# Horloge_Display.net
KiCad netlist of a schematic drawn in Altium Designer
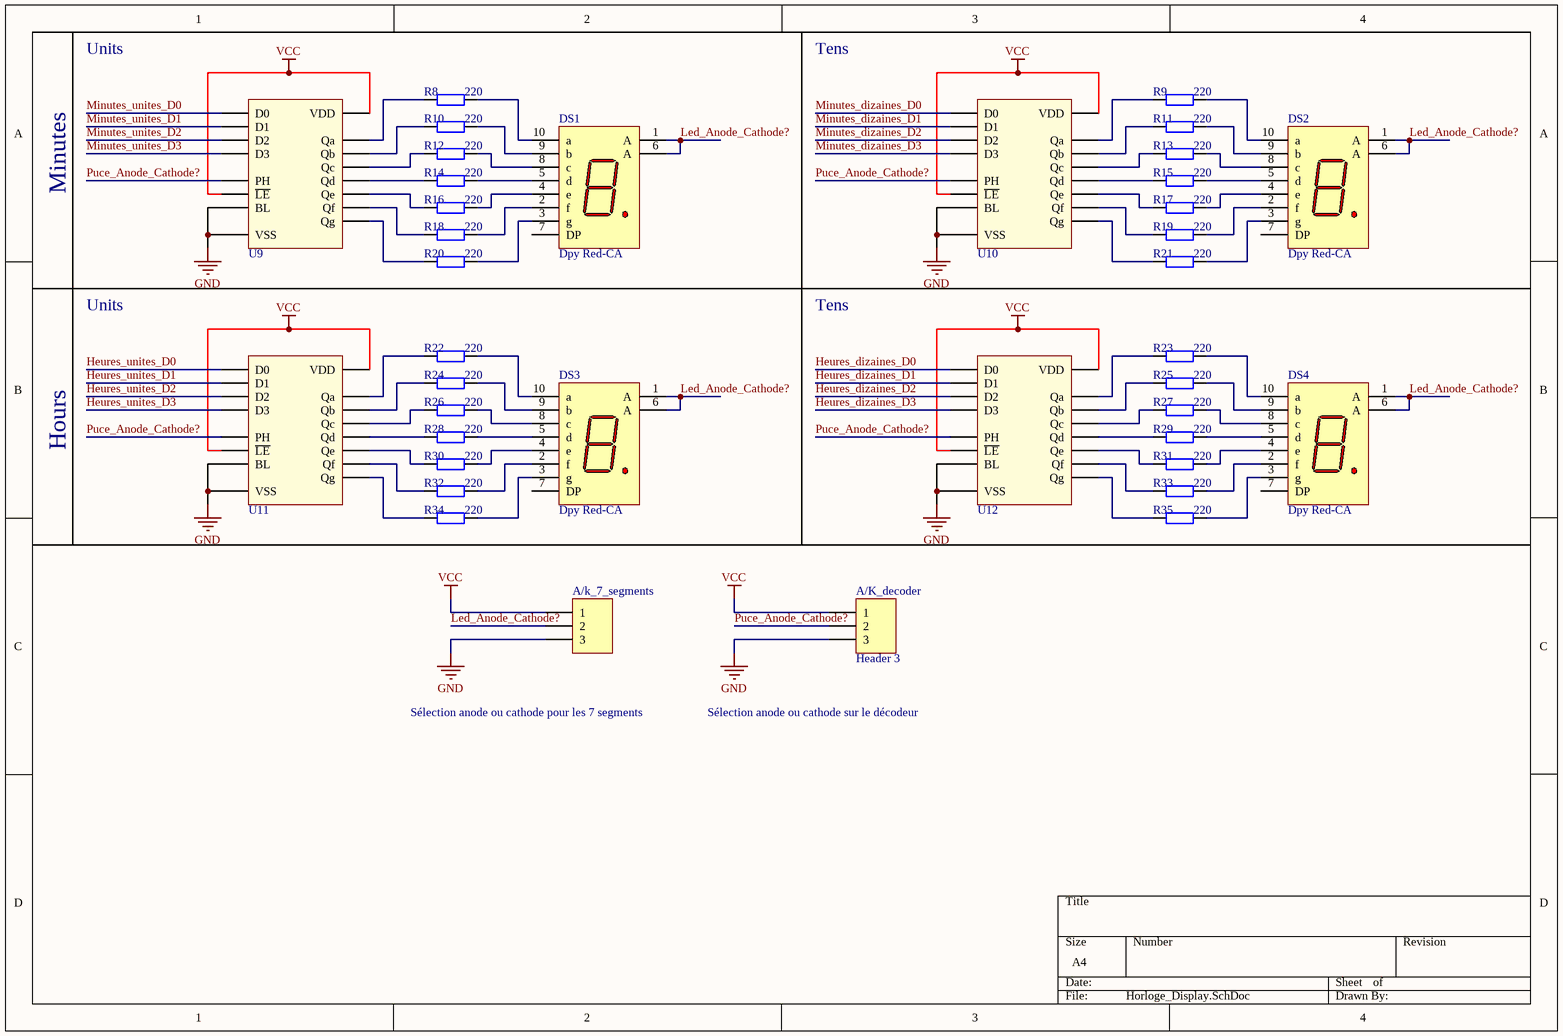
[diagram p0: Horloge_Display.SchDoc]

(export (version "E")
  (design (tool "Eeschema 10.0.6"))
  (components
    (comp (ref "A/k_7_segments")
      (value "Common_7-segments")
      (footprint "HDR1X3")
      (description "Header, 3-Pin")
      (fields (field (name "PUBLISHER") "Altium Limited"))
      (libsource (lib "Miscellaneous Connectors") (part "Header 3"))
    )
    (comp (ref "A/K_decoder")
      (value "Header 3")
      (footprint "HDR1X3")
      (description "Header, 3-Pin")
      (fields (field (name "PUBLISHER") "Altium Limited"))
      (libsource (lib "Miscellaneous Connectors") (part "Header 3"))
    )
    (comp (ref "DS1")
      (value "Dpy Red-CA")
      (footprint "7 segments 5082-7731")
      (description "7.62 mm Black Surface HER 7-Segment Display: CA, RH DP")
      (fields (field (name "PUBLISHER") "Altium Limited"))
      (libsource (lib "Miscellaneous Devices") (part "Dpy Red-CA"))
    )
    (comp (ref "DS2")
      (value "Dpy Red-CA")
      (footprint "7 segments 5082-7731")
      (description "7.62 mm Black Surface HER 7-Segment Display: CA, RH DP")
      (fields (field (name "PUBLISHER") "Altium Limited"))
      (libsource (lib "Miscellaneous Devices") (part "Dpy Red-CA"))
    )
    (comp (ref "DS3")
      (value "Dpy Red-CA")
      (footprint "7 segments 5082-7731")
      (description "7.62 mm Black Surface HER 7-Segment Display: CA, RH DP")
      (fields (field (name "PUBLISHER") "Altium Limited"))
      (libsource (lib "Miscellaneous Devices") (part "Dpy Red-CA"))
    )
    (comp (ref "DS4")
      (value "Dpy Red-CA")
      (footprint "7 segments 5082-7731")
      (description "7.62 mm Black Surface HER 7-Segment Display: CA, RH DP")
      (fields (field (name "PUBLISHER") "Altium Limited"))
      (libsource (lib "Miscellaneous Devices") (part "Dpy Red-CA"))
    )
    (comp (ref "R8")
      (value "220")
      (footprint "Resistor 1206")
      (description "Resistor")
      (fields (field (name "Comment") "Res2") (field (name "PUBLISHER") "Altium Limited"))
      (libsource (lib "Miscellaneous Devices") (part "Res2"))
    )
    (comp (ref "R9")
      (value "220")
      (footprint "Resistor 1206")
      (description "Resistor")
      (fields (field (name "Comment") "Res2") (field (name "PUBLISHER") "Altium Limited"))
      (libsource (lib "Miscellaneous Devices") (part "Res2"))
    )
    (comp (ref "R10")
      (value "220")
      (footprint "Resistor 1206")
      (description "Resistor")
      (fields (field (name "Comment") "Res2") (field (name "PUBLISHER") "Altium Limited"))
      (libsource (lib "Miscellaneous Devices") (part "Res2"))
    )
    (comp (ref "R11")
      (value "220")
      (footprint "Resistor 1206")
      (description "Resistor")
      (fields (field (name "Comment") "Res2") (field (name "PUBLISHER") "Altium Limited"))
      (libsource (lib "Miscellaneous Devices") (part "Res2"))
    )
    (comp (ref "R12")
      (value "220")
      (footprint "Resistor 1206")
      (description "Resistor")
      (fields (field (name "Comment") "Res2") (field (name "PUBLISHER") "Altium Limited"))
      (libsource (lib "Miscellaneous Devices") (part "Res2"))
    )
    (comp (ref "R13")
      (value "220")
      (footprint "Resistor 1206")
      (description "Resistor")
      (fields (field (name "Comment") "Res2") (field (name "PUBLISHER") "Altium Limited"))
      (libsource (lib "Miscellaneous Devices") (part "Res2"))
    )
    (comp (ref "R14")
      (value "220")
      (footprint "Resistor 1206")
      (description "Resistor")
      (fields (field (name "Comment") "Res2") (field (name "PUBLISHER") "Altium Limited"))
      (libsource (lib "Miscellaneous Devices") (part "Res2"))
    )
    (comp (ref "R15")
      (value "220")
      (footprint "Resistor 1206")
      (description "Resistor")
      (fields (field (name "Comment") "Res2") (field (name "PUBLISHER") "Altium Limited"))
      (libsource (lib "Miscellaneous Devices") (part "Res2"))
    )
    (comp (ref "R16")
      (value "220")
      (footprint "Resistor 1206")
      (description "Resistor")
      (fields (field (name "Comment") "Res2") (field (name "PUBLISHER") "Altium Limited"))
      (libsource (lib "Miscellaneous Devices") (part "Res2"))
    )
    (comp (ref "R17")
      (value "220")
      (footprint "Resistor 1206")
      (description "Resistor")
      (fields (field (name "Comment") "Res2") (field (name "PUBLISHER") "Altium Limited"))
      (libsource (lib "Miscellaneous Devices") (part "Res2"))
    )
    (comp (ref "R18")
      (value "220")
      (footprint "Resistor 1206")
      (description "Resistor")
      (fields (field (name "Comment") "Res2") (field (name "PUBLISHER") "Altium Limited"))
      (libsource (lib "Miscellaneous Devices") (part "Res2"))
    )
    (comp (ref "R19")
      (value "220")
      (footprint "Resistor 1206")
      (description "Resistor")
      (fields (field (name "Comment") "Res2") (field (name "PUBLISHER") "Altium Limited"))
      (libsource (lib "Miscellaneous Devices") (part "Res2"))
    )
    (comp (ref "R20")
      (value "220")
      (footprint "Resistor 1206")
      (description "Resistor")
      (fields (field (name "Comment") "Res2") (field (name "PUBLISHER") "Altium Limited"))
      (libsource (lib "Miscellaneous Devices") (part "Res2"))
    )
    (comp (ref "R21")
      (value "220")
      (footprint "Resistor 1206")
      (description "Resistor")
      (fields (field (name "Comment") "Res2") (field (name "PUBLISHER") "Altium Limited"))
      (libsource (lib "Miscellaneous Devices") (part "Res2"))
    )
    (comp (ref "R22")
      (value "220")
      (footprint "Resistor 1206")
      (description "Resistor")
      (fields (field (name "Comment") "Res2") (field (name "PUBLISHER") "Altium Limited"))
      (libsource (lib "Miscellaneous Devices") (part "Res2"))
    )
    (comp (ref "R23")
      (value "220")
      (footprint "Resistor 1206")
      (description "Resistor")
      (fields (field (name "Comment") "Res2") (field (name "PUBLISHER") "Altium Limited"))
      (libsource (lib "Miscellaneous Devices") (part "Res2"))
    )
    (comp (ref "R24")
      (value "220")
      (footprint "Resistor 1206")
      (description "Resistor")
      (fields (field (name "Comment") "Res2") (field (name "PUBLISHER") "Altium Limited"))
      (libsource (lib "Miscellaneous Devices") (part "Res2"))
    )
    (comp (ref "R25")
      (value "220")
      (footprint "Resistor 1206")
      (description "Resistor")
      (fields (field (name "Comment") "Res2") (field (name "PUBLISHER") "Altium Limited"))
      (libsource (lib "Miscellaneous Devices") (part "Res2"))
    )
    (comp (ref "R26")
      (value "220")
      (footprint "Resistor 1206")
      (description "Resistor")
      (fields (field (name "Comment") "Res2") (field (name "PUBLISHER") "Altium Limited"))
      (libsource (lib "Miscellaneous Devices") (part "Res2"))
    )
    (comp (ref "R27")
      (value "220")
      (footprint "Resistor 1206")
      (description "Resistor")
      (fields (field (name "Comment") "Res2") (field (name "PUBLISHER") "Altium Limited"))
      (libsource (lib "Miscellaneous Devices") (part "Res2"))
    )
    (comp (ref "R28")
      (value "220")
      (footprint "Resistor 1206")
      (description "Resistor")
      (fields (field (name "Comment") "Res2") (field (name "PUBLISHER") "Altium Limited"))
      (libsource (lib "Miscellaneous Devices") (part "Res2"))
    )
    (comp (ref "R29")
      (value "220")
      (footprint "Resistor 1206")
      (description "Resistor")
      (fields (field (name "Comment") "Res2") (field (name "PUBLISHER") "Altium Limited"))
      (libsource (lib "Miscellaneous Devices") (part "Res2"))
    )
    (comp (ref "R30")
      (value "220")
      (footprint "Resistor 1206")
      (description "Resistor")
      (fields (field (name "Comment") "Res2") (field (name "PUBLISHER") "Altium Limited"))
      (libsource (lib "Miscellaneous Devices") (part "Res2"))
    )
    (comp (ref "R31")
      (value "220")
      (footprint "Resistor 1206")
      (description "Resistor")
      (fields (field (name "Comment") "Res2") (field (name "PUBLISHER") "Altium Limited"))
      (libsource (lib "Miscellaneous Devices") (part "Res2"))
    )
    (comp (ref "R32")
      (value "220")
      (footprint "Resistor 1206")
      (description "Resistor")
      (fields (field (name "Comment") "Res2") (field (name "PUBLISHER") "Altium Limited"))
      (libsource (lib "Miscellaneous Devices") (part "Res2"))
    )
    (comp (ref "R33")
      (value "220")
      (footprint "Resistor 1206")
      (description "Resistor")
      (fields (field (name "Comment") "Res2") (field (name "PUBLISHER") "Altium Limited"))
      (libsource (lib "Miscellaneous Devices") (part "Res2"))
    )
    (comp (ref "R34")
      (value "220")
      (footprint "Resistor 1206")
      (description "Resistor")
      (fields (field (name "Comment") "Res2") (field (name "PUBLISHER") "Altium Limited"))
      (libsource (lib "Miscellaneous Devices") (part "Res2"))
    )
    (comp (ref "R35")
      (value "220")
      (footprint "Resistor 1206")
      (description "Resistor")
      (fields (field (name "Comment") "Res2") (field (name "PUBLISHER") "Altium Limited"))
      (libsource (lib "Miscellaneous Devices") (part "Res2"))
    )
    (comp (ref "U9")
      (value "7 segment driver")
      (footprint "HEF4543")
      (libsource (lib "Robot_2020") (part "HEF4543B"))
    )
    (comp (ref "U10")
      (value "7 segment driver")
      (footprint "HEF4543")
      (libsource (lib "Robot_2020") (part "HEF4543B"))
    )
    (comp (ref "U11")
      (value "7 segment driver")
      (footprint "HEF4543")
      (libsource (lib "Robot_2020") (part "HEF4543B"))
    )
    (comp (ref "U12")
      (value "7 segment driver")
      (footprint "HEF4543")
      (libsource (lib "Robot_2020") (part "HEF4543B"))
    )
  )
  (nets
    (net (code "1") (name "/Heures_dizaines_D0") (class "Default")
      (node (ref "U12") (pin "5") (pinfunction "D0_5") (pintype "passive"))
    )
    (net (code "2") (name "/Heures_dizaines_D1") (class "Default")
      (node (ref "U12") (pin "3") (pinfunction "D1_3") (pintype "passive"))
    )
    (net (code "3") (name "/Heures_dizaines_D2") (class "Default")
      (node (ref "U12") (pin "2") (pinfunction "D2_2") (pintype "passive"))
    )
    (net (code "4") (name "/Heures_dizaines_D3") (class "Default")
      (node (ref "U12") (pin "4") (pinfunction "D3_4") (pintype "passive"))
    )
    (net (code "5") (name "/Heures_unites_D0") (class "Default")
      (node (ref "U11") (pin "5") (pinfunction "D0_5") (pintype "passive"))
    )
    (net (code "6") (name "/Heures_unites_D1") (class "Default")
      (node (ref "U11") (pin "3") (pinfunction "D1_3") (pintype "passive"))
    )
    (net (code "7") (name "/Heures_unites_D2") (class "Default")
      (node (ref "U11") (pin "2") (pinfunction "D2_2") (pintype "passive"))
    )
    (net (code "8") (name "/Heures_unites_D3") (class "Default")
      (node (ref "U11") (pin "4") (pinfunction "D3_4") (pintype "passive"))
    )
    (net (code "9") (name "/Led_Anode_Cathode?") (class "Default")
      (node (ref "A/k_7_segments") (pin "2") (pinfunction "2_2") (pintype "passive"))
      (node (ref "DS1") (pin "1") (pinfunction "A_1") (pintype "passive"))
      (node (ref "DS1") (pin "6") (pinfunction "A_6") (pintype "passive"))
      (node (ref "DS2") (pin "1") (pinfunction "A_1") (pintype "passive"))
      (node (ref "DS2") (pin "6") (pinfunction "A_6") (pintype "passive"))
      (node (ref "DS3") (pin "1") (pinfunction "A_1") (pintype "passive"))
      (node (ref "DS3") (pin "6") (pinfunction "A_6") (pintype "passive"))
      (node (ref "DS4") (pin "1") (pinfunction "A_1") (pintype "passive"))
      (node (ref "DS4") (pin "6") (pinfunction "A_6") (pintype "passive"))
    )
    (net (code "10") (name "/Minutes_dizaines_D0") (class "Default")
      (node (ref "U10") (pin "5") (pinfunction "D0_5") (pintype "passive"))
    )
    (net (code "11") (name "/Minutes_dizaines_D1") (class "Default")
      (node (ref "U10") (pin "3") (pinfunction "D1_3") (pintype "passive"))
    )
    (net (code "12") (name "/Minutes_dizaines_D2") (class "Default")
      (node (ref "U10") (pin "2") (pinfunction "D2_2") (pintype "passive"))
    )
    (net (code "13") (name "/Minutes_dizaines_D3") (class "Default")
      (node (ref "U10") (pin "4") (pinfunction "D3_4") (pintype "passive"))
    )
    (net (code "14") (name "/Minutes_unites_D0") (class "Default")
      (node (ref "U9") (pin "5") (pinfunction "D0_5") (pintype "passive"))
    )
    (net (code "15") (name "/Minutes_unites_D1") (class "Default")
      (node (ref "U9") (pin "3") (pinfunction "D1_3") (pintype "passive"))
    )
    (net (code "16") (name "/Minutes_unites_D2") (class "Default")
      (node (ref "U9") (pin "2") (pinfunction "D2_2") (pintype "passive"))
    )
    (net (code "17") (name "/Minutes_unites_D3") (class "Default")
      (node (ref "U9") (pin "4") (pinfunction "D3_4") (pintype "passive"))
    )
    (net (code "18") (name "/Puce_Anode_Cathode?") (class "Default")
      (node (ref "A/K_decoder") (pin "2") (pinfunction "2_2") (pintype "passive"))
      (node (ref "U10") (pin "6") (pinfunction "PH_6") (pintype "passive"))
      (node (ref "U11") (pin "6") (pinfunction "PH_6") (pintype "passive"))
      (node (ref "U12") (pin "6") (pinfunction "PH_6") (pintype "passive"))
      (node (ref "U9") (pin "6") (pinfunction "PH_6") (pintype "passive"))
    )
    (net (code "19") (name "GND") (class "Default")
      (node (ref "A/K_decoder") (pin "3") (pinfunction "3_3") (pintype "passive"))
      (node (ref "A/k_7_segments") (pin "3") (pinfunction "3_3") (pintype "passive"))
      (node (ref "U10") (pin "7") (pinfunction "BL_7") (pintype "passive"))
      (node (ref "U10") (pin "8") (pinfunction "VSS_8") (pintype "passive"))
      (node (ref "U11") (pin "7") (pinfunction "BL_7") (pintype "passive"))
      (node (ref "U11") (pin "8") (pinfunction "VSS_8") (pintype "passive"))
      (node (ref "U12") (pin "7") (pinfunction "BL_7") (pintype "passive"))
      (node (ref "U12") (pin "8") (pinfunction "VSS_8") (pintype "passive"))
      (node (ref "U9") (pin "7") (pinfunction "BL_7") (pintype "passive"))
      (node (ref "U9") (pin "8") (pinfunction "VSS_8") (pintype "passive"))
    )
    (net (code "20") (name "Net-(DS1-a)") (class "Default")
      (node (ref "DS1") (pin "10") (pinfunction "a_10") (pintype "passive"))
      (node (ref "R8") (pin "2") (pinfunction "2_2") (pintype "passive"))
    )
    (net (code "21") (name "Net-(DS1-b)") (class "Default")
      (node (ref "DS1") (pin "9") (pinfunction "b_9") (pintype "passive"))
      (node (ref "R10") (pin "2") (pinfunction "2_2") (pintype "passive"))
    )
    (net (code "22") (name "Net-(DS1-c)") (class "Default")
      (node (ref "DS1") (pin "8") (pinfunction "c_8") (pintype "passive"))
      (node (ref "R12") (pin "2") (pinfunction "2_2") (pintype "passive"))
    )
    (net (code "23") (name "Net-(DS1-d)") (class "Default")
      (node (ref "DS1") (pin "5") (pinfunction "d_5") (pintype "passive"))
      (node (ref "R14") (pin "2") (pinfunction "2_2") (pintype "passive"))
    )
    (net (code "24") (name "Net-(DS1-e)") (class "Default")
      (node (ref "DS1") (pin "4") (pinfunction "e_4") (pintype "passive"))
      (node (ref "R16") (pin "2") (pinfunction "2_2") (pintype "passive"))
    )
    (net (code "25") (name "Net-(DS1-f)") (class "Default")
      (node (ref "DS1") (pin "2") (pinfunction "f_2") (pintype "passive"))
      (node (ref "R18") (pin "2") (pinfunction "2_2") (pintype "passive"))
    )
    (net (code "26") (name "Net-(DS1-g)") (class "Default")
      (node (ref "DS1") (pin "3") (pinfunction "g_3") (pintype "passive"))
      (node (ref "R20") (pin "2") (pinfunction "2_2") (pintype "passive"))
    )
    (net (code "27") (name "Net-(DS2-a)") (class "Default")
      (node (ref "DS2") (pin "10") (pinfunction "a_10") (pintype "passive"))
      (node (ref "R9") (pin "2") (pinfunction "2_2") (pintype "passive"))
    )
    (net (code "28") (name "Net-(DS2-b)") (class "Default")
      (node (ref "DS2") (pin "9") (pinfunction "b_9") (pintype "passive"))
      (node (ref "R11") (pin "2") (pinfunction "2_2") (pintype "passive"))
    )
    (net (code "29") (name "Net-(DS2-c)") (class "Default")
      (node (ref "DS2") (pin "8") (pinfunction "c_8") (pintype "passive"))
      (node (ref "R13") (pin "2") (pinfunction "2_2") (pintype "passive"))
    )
    (net (code "30") (name "Net-(DS2-d)") (class "Default")
      (node (ref "DS2") (pin "5") (pinfunction "d_5") (pintype "passive"))
      (node (ref "R15") (pin "2") (pinfunction "2_2") (pintype "passive"))
    )
    (net (code "31") (name "Net-(DS2-e)") (class "Default")
      (node (ref "DS2") (pin "4") (pinfunction "e_4") (pintype "passive"))
      (node (ref "R17") (pin "2") (pinfunction "2_2") (pintype "passive"))
    )
    (net (code "32") (name "Net-(DS2-f)") (class "Default")
      (node (ref "DS2") (pin "2") (pinfunction "f_2") (pintype "passive"))
      (node (ref "R19") (pin "2") (pinfunction "2_2") (pintype "passive"))
    )
    (net (code "33") (name "Net-(DS2-g)") (class "Default")
      (node (ref "DS2") (pin "3") (pinfunction "g_3") (pintype "passive"))
      (node (ref "R21") (pin "2") (pinfunction "2_2") (pintype "passive"))
    )
    (net (code "34") (name "Net-(DS3-a)") (class "Default")
      (node (ref "DS3") (pin "10") (pinfunction "a_10") (pintype "passive"))
      (node (ref "R22") (pin "2") (pinfunction "2_2") (pintype "passive"))
    )
    (net (code "35") (name "Net-(DS3-b)") (class "Default")
      (node (ref "DS3") (pin "9") (pinfunction "b_9") (pintype "passive"))
      (node (ref "R24") (pin "2") (pinfunction "2_2") (pintype "passive"))
    )
    (net (code "36") (name "Net-(DS3-c)") (class "Default")
      (node (ref "DS3") (pin "8") (pinfunction "c_8") (pintype "passive"))
      (node (ref "R26") (pin "2") (pinfunction "2_2") (pintype "passive"))
    )
    (net (code "37") (name "Net-(DS3-d)") (class "Default")
      (node (ref "DS3") (pin "5") (pinfunction "d_5") (pintype "passive"))
      (node (ref "R28") (pin "2") (pinfunction "2_2") (pintype "passive"))
    )
    (net (code "38") (name "Net-(DS3-e)") (class "Default")
      (node (ref "DS3") (pin "4") (pinfunction "e_4") (pintype "passive"))
      (node (ref "R30") (pin "2") (pinfunction "2_2") (pintype "passive"))
    )
    (net (code "39") (name "Net-(DS3-f)") (class "Default")
      (node (ref "DS3") (pin "2") (pinfunction "f_2") (pintype "passive"))
      (node (ref "R32") (pin "2") (pinfunction "2_2") (pintype "passive"))
    )
    (net (code "40") (name "Net-(DS3-g)") (class "Default")
      (node (ref "DS3") (pin "3") (pinfunction "g_3") (pintype "passive"))
      (node (ref "R34") (pin "2") (pinfunction "2_2") (pintype "passive"))
    )
    (net (code "41") (name "Net-(DS4-a)") (class "Default")
      (node (ref "DS4") (pin "10") (pinfunction "a_10") (pintype "passive"))
      (node (ref "R23") (pin "2") (pinfunction "2_2") (pintype "passive"))
    )
    (net (code "42") (name "Net-(DS4-b)") (class "Default")
      (node (ref "DS4") (pin "9") (pinfunction "b_9") (pintype "passive"))
      (node (ref "R25") (pin "2") (pinfunction "2_2") (pintype "passive"))
    )
    (net (code "43") (name "Net-(DS4-c)") (class "Default")
      (node (ref "DS4") (pin "8") (pinfunction "c_8") (pintype "passive"))
      (node (ref "R27") (pin "2") (pinfunction "2_2") (pintype "passive"))
    )
    (net (code "44") (name "Net-(DS4-d)") (class "Default")
      (node (ref "DS4") (pin "5") (pinfunction "d_5") (pintype "passive"))
      (node (ref "R29") (pin "2") (pinfunction "2_2") (pintype "passive"))
    )
    (net (code "45") (name "Net-(DS4-e)") (class "Default")
      (node (ref "DS4") (pin "4") (pinfunction "e_4") (pintype "passive"))
      (node (ref "R31") (pin "2") (pinfunction "2_2") (pintype "passive"))
    )
    (net (code "46") (name "Net-(DS4-f)") (class "Default")
      (node (ref "DS4") (pin "2") (pinfunction "f_2") (pintype "passive"))
      (node (ref "R33") (pin "2") (pinfunction "2_2") (pintype "passive"))
    )
    (net (code "47") (name "Net-(DS4-g)") (class "Default")
      (node (ref "DS4") (pin "3") (pinfunction "g_3") (pintype "passive"))
      (node (ref "R35") (pin "2") (pinfunction "2_2") (pintype "passive"))
    )
    (net (code "48") (name "Net-(U9-Qa)") (class "Default")
      (node (ref "R8") (pin "1") (pinfunction "1_1") (pintype "passive"))
      (node (ref "U9") (pin "9") (pinfunction "Qa_9") (pintype "passive"))
    )
    (net (code "49") (name "Net-(U9-Qb)") (class "Default")
      (node (ref "R10") (pin "1") (pinfunction "1_1") (pintype "passive"))
      (node (ref "U9") (pin "10") (pinfunction "Qb_10") (pintype "passive"))
    )
    (net (code "50") (name "Net-(U9-Qc)") (class "Default")
      (node (ref "R12") (pin "1") (pinfunction "1_1") (pintype "passive"))
      (node (ref "U9") (pin "11") (pinfunction "Qc_11") (pintype "passive"))
    )
    (net (code "51") (name "Net-(U9-Qd)") (class "Default")
      (node (ref "R14") (pin "1") (pinfunction "1_1") (pintype "passive"))
      (node (ref "U9") (pin "12") (pinfunction "Qd_12") (pintype "passive"))
    )
    (net (code "52") (name "Net-(U9-Qe)") (class "Default")
      (node (ref "R16") (pin "1") (pinfunction "1_1") (pintype "passive"))
      (node (ref "U9") (pin "13") (pinfunction "Qe_13") (pintype "passive"))
    )
    (net (code "53") (name "Net-(U9-Qf)") (class "Default")
      (node (ref "R18") (pin "1") (pinfunction "1_1") (pintype "passive"))
      (node (ref "U9") (pin "15") (pinfunction "Qf_15") (pintype "passive"))
    )
    (net (code "54") (name "Net-(U9-Qg)") (class "Default")
      (node (ref "R20") (pin "1") (pinfunction "1_1") (pintype "passive"))
      (node (ref "U9") (pin "14") (pinfunction "Qg_14") (pintype "passive"))
    )
    (net (code "55") (name "Net-(U10-Qa)") (class "Default")
      (node (ref "R9") (pin "1") (pinfunction "1_1") (pintype "passive"))
      (node (ref "U10") (pin "9") (pinfunction "Qa_9") (pintype "passive"))
    )
    (net (code "56") (name "Net-(U10-Qb)") (class "Default")
      (node (ref "R11") (pin "1") (pinfunction "1_1") (pintype "passive"))
      (node (ref "U10") (pin "10") (pinfunction "Qb_10") (pintype "passive"))
    )
    (net (code "57") (name "Net-(U10-Qc)") (class "Default")
      (node (ref "R13") (pin "1") (pinfunction "1_1") (pintype "passive"))
      (node (ref "U10") (pin "11") (pinfunction "Qc_11") (pintype "passive"))
    )
    (net (code "58") (name "Net-(U10-Qd)") (class "Default")
      (node (ref "R15") (pin "1") (pinfunction "1_1") (pintype "passive"))
      (node (ref "U10") (pin "12") (pinfunction "Qd_12") (pintype "passive"))
    )
    (net (code "59") (name "Net-(U10-Qe)") (class "Default")
      (node (ref "R17") (pin "1") (pinfunction "1_1") (pintype "passive"))
      (node (ref "U10") (pin "13") (pinfunction "Qe_13") (pintype "passive"))
    )
    (net (code "60") (name "Net-(U10-Qf)") (class "Default")
      (node (ref "R19") (pin "1") (pinfunction "1_1") (pintype "passive"))
      (node (ref "U10") (pin "15") (pinfunction "Qf_15") (pintype "passive"))
    )
    (net (code "61") (name "Net-(U10-Qg)") (class "Default")
      (node (ref "R21") (pin "1") (pinfunction "1_1") (pintype "passive"))
      (node (ref "U10") (pin "14") (pinfunction "Qg_14") (pintype "passive"))
    )
    (net (code "62") (name "Net-(U11-Qa)") (class "Default")
      (node (ref "R22") (pin "1") (pinfunction "1_1") (pintype "passive"))
      (node (ref "U11") (pin "9") (pinfunction "Qa_9") (pintype "passive"))
    )
    (net (code "63") (name "Net-(U11-Qb)") (class "Default")
      (node (ref "R24") (pin "1") (pinfunction "1_1") (pintype "passive"))
      (node (ref "U11") (pin "10") (pinfunction "Qb_10") (pintype "passive"))
    )
    (net (code "64") (name "Net-(U11-Qc)") (class "Default")
      (node (ref "R26") (pin "1") (pinfunction "1_1") (pintype "passive"))
      (node (ref "U11") (pin "11") (pinfunction "Qc_11") (pintype "passive"))
    )
    (net (code "65") (name "Net-(U11-Qd)") (class "Default")
      (node (ref "R28") (pin "1") (pinfunction "1_1") (pintype "passive"))
      (node (ref "U11") (pin "12") (pinfunction "Qd_12") (pintype "passive"))
    )
    (net (code "66") (name "Net-(U11-Qe)") (class "Default")
      (node (ref "R30") (pin "1") (pinfunction "1_1") (pintype "passive"))
      (node (ref "U11") (pin "13") (pinfunction "Qe_13") (pintype "passive"))
    )
    (net (code "67") (name "Net-(U11-Qf)") (class "Default")
      (node (ref "R32") (pin "1") (pinfunction "1_1") (pintype "passive"))
      (node (ref "U11") (pin "15") (pinfunction "Qf_15") (pintype "passive"))
    )
    (net (code "68") (name "Net-(U11-Qg)") (class "Default")
      (node (ref "R34") (pin "1") (pinfunction "1_1") (pintype "passive"))
      (node (ref "U11") (pin "14") (pinfunction "Qg_14") (pintype "passive"))
    )
    (net (code "69") (name "Net-(U12-Qa)") (class "Default")
      (node (ref "R23") (pin "1") (pinfunction "1_1") (pintype "passive"))
      (node (ref "U12") (pin "9") (pinfunction "Qa_9") (pintype "passive"))
    )
    (net (code "70") (name "Net-(U12-Qb)") (class "Default")
      (node (ref "R25") (pin "1") (pinfunction "1_1") (pintype "passive"))
      (node (ref "U12") (pin "10") (pinfunction "Qb_10") (pintype "passive"))
    )
    (net (code "71") (name "Net-(U12-Qc)") (class "Default")
      (node (ref "R27") (pin "1") (pinfunction "1_1") (pintype "passive"))
      (node (ref "U12") (pin "11") (pinfunction "Qc_11") (pintype "passive"))
    )
    (net (code "72") (name "Net-(U12-Qd)") (class "Default")
      (node (ref "R29") (pin "1") (pinfunction "1_1") (pintype "passive"))
      (node (ref "U12") (pin "12") (pinfunction "Qd_12") (pintype "passive"))
    )
    (net (code "73") (name "Net-(U12-Qe)") (class "Default")
      (node (ref "R31") (pin "1") (pinfunction "1_1") (pintype "passive"))
      (node (ref "U12") (pin "13") (pinfunction "Qe_13") (pintype "passive"))
    )
    (net (code "74") (name "Net-(U12-Qf)") (class "Default")
      (node (ref "R33") (pin "1") (pinfunction "1_1") (pintype "passive"))
      (node (ref "U12") (pin "15") (pinfunction "Qf_15") (pintype "passive"))
    )
    (net (code "75") (name "Net-(U12-Qg)") (class "Default")
      (node (ref "R35") (pin "1") (pinfunction "1_1") (pintype "passive"))
      (node (ref "U12") (pin "14") (pinfunction "Qg_14") (pintype "passive"))
    )
    (net (code "76") (name "VCC") (class "Default")
      (node (ref "A/K_decoder") (pin "1") (pinfunction "1_1") (pintype "passive"))
      (node (ref "A/k_7_segments") (pin "1") (pinfunction "1_1") (pintype "passive"))
      (node (ref "U10") (pin "1") (pinfunction "~{LE}_1") (pintype "passive"))
      (node (ref "U10") (pin "16") (pinfunction "VDD_16") (pintype "passive"))
      (node (ref "U11") (pin "1") (pinfunction "~{LE}_1") (pintype "passive"))
      (node (ref "U11") (pin "16") (pinfunction "VDD_16") (pintype "passive"))
      (node (ref "U12") (pin "1") (pinfunction "~{LE}_1") (pintype "passive"))
      (node (ref "U12") (pin "16") (pinfunction "VDD_16") (pintype "passive"))
      (node (ref "U9") (pin "1") (pinfunction "~{LE}_1") (pintype "passive"))
      (node (ref "U9") (pin "16") (pinfunction "VDD_16") (pintype "passive"))
    )
    (net (code "77") (name "unconnected-(DS1-DP-Pad7)") (class "Default")
      (node (ref "DS1") (pin "7") (pinfunction "DP_7") (pintype "passive"))
    )
    (net (code "78") (name "unconnected-(DS2-DP-Pad7)") (class "Default")
      (node (ref "DS2") (pin "7") (pinfunction "DP_7") (pintype "passive"))
    )
    (net (code "79") (name "unconnected-(DS3-DP-Pad7)") (class "Default")
      (node (ref "DS3") (pin "7") (pinfunction "DP_7") (pintype "passive"))
    )
    (net (code "80") (name "unconnected-(DS4-DP-Pad7)") (class "Default")
      (node (ref "DS4") (pin "7") (pinfunction "DP_7") (pintype "passive"))
    )
  )
)
